# Sheet2.net
KiCad netlist of a schematic drawn in Altium Designer
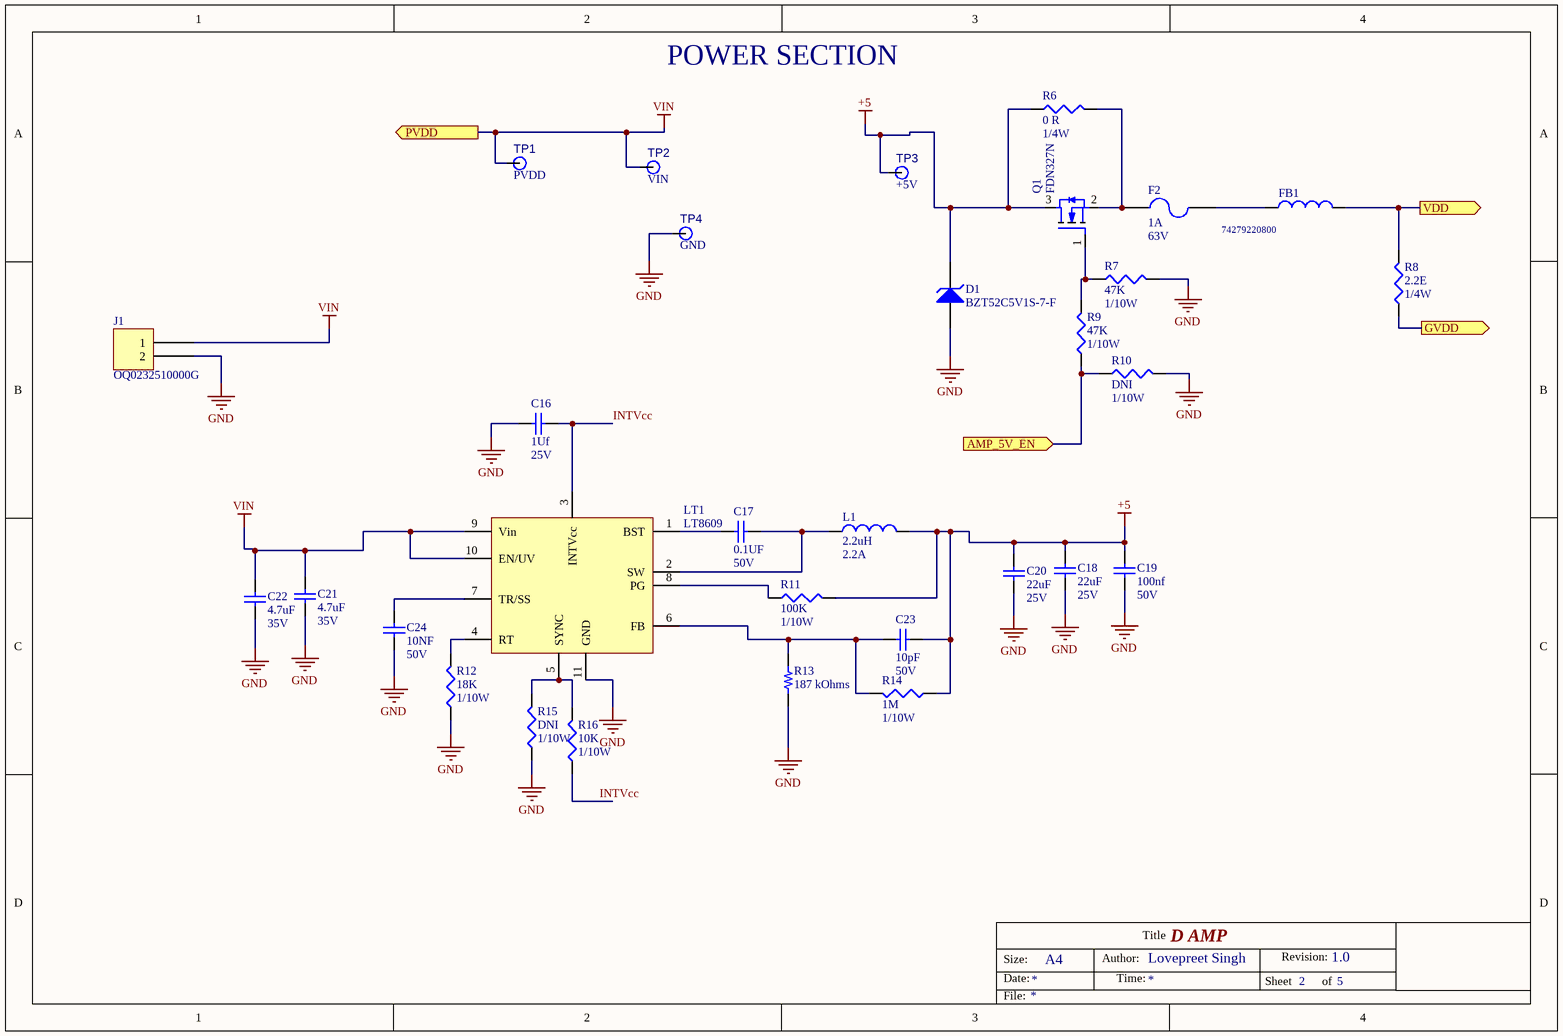
[diagram p0: Sheet2.SchDoc]

(export (version "E")
  (design (tool "Eeschema 10.0.6"))
  (components
    (comp (ref "C16")
      (value "1Uf")
      (footprint "C0603")
      (description "CAP MLCC SMD 25V 1uF 10% X7R 0603")
      (fields (field (name "VRATING") "25V"))
      (libsource (lib "Database_Libs1") (part "CAP_NPOL"))
    )
    (comp (ref "C17")
      (value "0.1UF")
      (footprint "2P0603R")
      (description "CAP CER 0.1UF 10% 50V X7R 0603")
      (fields (field (name "VRATING") "50V"))
      (libsource (lib "Database_Libs1") (part "CAP_NPOL"))
    )
    (comp (ref "C18")
      (value "22uF")
      (footprint "C1206")
      (description "CAP CER 22uF 20% 25V X5R 1206")
      (fields (field (name "VRATING") "25V"))
      (libsource (lib "Database_Libs1") (part "CAP_NPOL"))
    )
    (comp (ref "C19")
      (value "100nf")
      (footprint "C0603")
      (description "CAP CER 100NF 10% 50V X7R 0603")
      (fields (field (name "VRATING") "50V"))
      (libsource (lib "Database_Libs1") (part "CAP_NPOL"))
    )
    (comp (ref "C20")
      (value "22uF")
      (footprint "C1206")
      (description "CAP CER 22uF 20% 25V X5R 1206")
      (fields (field (name "VRATING") "25V"))
      (libsource (lib "Database_Libs1") (part "CAP_NPOL"))
    )
    (comp (ref "C21")
      (value "4.7uF")
      (footprint "C0603")
      (description "CAP CER 4.7UF 20% 35V X5R 0603")
      (fields (field (name "VRATING") "35V"))
      (libsource (lib "Database_Libs1") (part "CAP_NPOL"))
    )
    (comp (ref "C22")
      (value "4.7uF")
      (footprint "C0603")
      (description "CAP CER 4.7UF 20% 35V X5R 0603")
      (fields (field (name "VRATING") "35V"))
      (libsource (lib "Database_Libs1") (part "CAP_NPOL"))
    )
    (comp (ref "C23")
      (value "10pF")
      (footprint "C0603")
      (description "CAP 10PF 5% 50V 0603")
      (fields (field (name "VRATING") "50V"))
      (libsource (lib "Database_Libs1") (part "CAP_NPOL"))
    )
    (comp (ref "C24")
      (value "10NF")
      (footprint "C0603")
      (description "CAP CER 10NF 10% 50V X7R 0603")
      (fields (field (name "VRATING") "50V"))
      (libsource (lib "Database_Libs1") (part "CAP_NPOL"))
    )
    (comp (ref "D1")
      (value "BZT52C5V1S-7-F")
      (footprint "SOD-323")
      (description "DIODE ZENER 5.1V 200MW SOD323")
      (libsource (lib "Database_Libs1") (part "DIODE_ZENER"))
    )
    (comp (ref "F2")
      (value "1A")
      (footprint "FUSE1206")
      (description "Fuse 1A 63V Slow Blow SMD 1206")
      (fields (field (name "VRATING") "63V"))
      (libsource (lib "Database_Libs1") (part "Fuse"))
    )
    (comp (ref "FB1")
      (value "74279220800")
      (footprint "L0805")
      (description "IND FERRITE CHIP 80 OHM 4A 0805")
      (libsource (lib "Database_Libs1") (part "FERRITE CHIP"))
    )
    (comp (ref "J1")
      (value "OQ0232510000G")
      (footprint "FCI 06-381-2PIN")
      (description "TERM BLOCK HDR 2POS 90DEG 3.81MM")
      (fields (field (name "MANUFACTURER") "Amphenol Anytek"))
      (libsource (lib "Celestial Altium Library - altium_library") (part "2 Pin"))
    )
    (comp (ref "L1")
      (value "2.2uH")
      (footprint "CDMC252012")
      (description "FIXED IND 2.2UH 2A 168 MOHM SMD")
      (fields (field (name "IRATING") "2.2A"))
      (libsource (lib "Database_Libs1") (part "INDUCTOR"))
    )
    (comp (ref "LT1")
      (value "LT8609")
      (footprint "MSOP-10")
      (description "IC SWTCH REG O/P ADJ 3A I/P 4.5V-42V SMD 10MSOP")
      (libsource (lib "Database_Libs1") (part "LT8609"))
    )
    (comp (ref "Q1")
      (value "FDN327N")
      (footprint "SOT23_123")
      (description "MOSFET N-CH 20V 2A SSOT-3")
      (libsource (lib "Database_Libs1") (part "MOSFET N-CH, 20V, 1.3A SOT-23"))
    )
    (comp (ref "R6")
      (value "0 R")
      (footprint "R1206")
      (description "RES SMD 0E 5% 1/4W 1206")
      (fields (field (name "PRATING") "1/4W"))
      (libsource (lib "Database_Libs1") (part "RES"))
    )
    (comp (ref "R7")
      (value "47K")
      (footprint "R0603")
      (description "RES SMD  47K 1% 1/10W 0603")
      (fields (field (name "PRATING") "1/10W"))
      (libsource (lib "Database_Libs1") (part "RES"))
    )
    (comp (ref "R8")
      (value "2.2E")
      (footprint "R1206")
      (description "RES SMD 2.2E 1% 1/4W 1206")
      (fields (field (name "PRATING") "1/4W"))
      (libsource (lib "Database_Libs1") (part "RES"))
    )
    (comp (ref "R9")
      (value "47K")
      (footprint "R0603")
      (description "RES SMD  47K 1% 1/10W 0603")
      (fields (field (name "PRATING") "1/10W"))
      (libsource (lib "Database_Libs1") (part "RES"))
    )
    (comp (ref "R10")
      (value "DNI")
      (footprint "R0603")
      (description "RES SMD DNI 0603")
      (fields (field (name "PRATING") "1/10W"))
      (libsource (lib "Database_Libs1") (part "RES_DNI"))
    )
    (comp (ref "R11")
      (value "100K")
      (footprint "R0603")
      (description "RES SMD 100K 1% 1/10W 0603")
      (fields (field (name "PRATING") "1/10W"))
      (libsource (lib "Database_Libs1") (part "RES"))
    )
    (comp (ref "R12")
      (value "18K")
      (footprint "R0603")
      (description "RES 18K OHM 1% 1/10W 0603")
      (fields (field (name "PRATING") "1/10W"))
      (libsource (lib "Database_Libs1") (part "RES"))
    )
    (comp (ref "R13")
      (value "187 kOhms")
      (footprint "RES 0603_1608")
      (description "RES SMD 187K OHM 0.5% 1/10W 0603")
      (fields (field (name "PART NUMBER") "RT0603DRE07187KL") (field (name "MANUFACTURER") "Yageo"))
      (libsource (lib "Celestial Altium Library - altium_library") (part "Resistor"))
    )
    (comp (ref "R14")
      (value "1M")
      (footprint "R0603")
      (description "RES SMD 1M 1% 1/10W 0603")
      (fields (field (name "PRATING") "1/10W"))
      (libsource (lib "Database_Libs1") (part "RES"))
    )
    (comp (ref "R15")
      (value "DNI")
      (footprint "R0603")
      (description "RES SMD DNI 0603")
      (fields (field (name "PRATING") "1/10W"))
      (libsource (lib "Database_Libs1") (part "RES_DNI"))
    )
    (comp (ref "R16")
      (value "10K")
      (footprint "R0603")
      (description "RES SMD 10K 1% 1/10W 0603")
      (fields (field (name "PRATING") "1/10W"))
      (libsource (lib "Database_Libs1") (part "RES"))
    )
    (comp (ref "TP1")
      (value "PVDD")
      (footprint "TP_THROUGH")
      (description "TEST_POINT_THROUGH")
      (libsource (lib "Database_Libs1") (part "TEST_POINT_THROUGH"))
    )
    (comp (ref "TP2")
      (value "VIN")
      (footprint "TP_THROUGH")
      (description "TEST_POINT_THROUGH")
      (libsource (lib "Database_Libs1") (part "TEST_POINT_THROUGH"))
    )
    (comp (ref "TP3")
      (value "+5V")
      (footprint "TP_THROUGH")
      (description "TEST_POINT_THROUGH")
      (libsource (lib "Database_Libs1") (part "TEST_POINT_THROUGH"))
    )
    (comp (ref "TP4")
      (value "GND")
      (footprint "TP_THROUGH")
      (description "TEST_POINT_THROUGH")
      (libsource (lib "Database_Libs1") (part "TEST_POINT_THROUGH"))
    )
  )
  (nets
    (net (code "1") (name "+5") (class "Default")
      (node (ref "C18") (pin "2") (pinfunction "2_2") (pintype "passive"))
      (node (ref "C19") (pin "2") (pinfunction "2_2") (pintype "passive"))
      (node (ref "C20") (pin "2") (pinfunction "2_2") (pintype "passive"))
      (node (ref "C23") (pin "2") (pinfunction "2_2") (pintype "passive"))
      (node (ref "D1") (pin "K") (pinfunction "K_K") (pintype "passive"))
      (node (ref "L1") (pin "2") (pinfunction "2_2") (pintype "passive"))
      (node (ref "Q1") (pin "3") (pinfunction "D_3") (pintype "passive"))
      (node (ref "R11") (pin "2") (pinfunction "2_2") (pintype "passive"))
      (node (ref "R14") (pin "1") (pinfunction "1_1") (pintype "passive"))
      (node (ref "R6") (pin "1") (pinfunction "1_1") (pintype "passive"))
      (node (ref "TP3") (pin "1") (pinfunction "1_1") (pintype "passive"))
    )
    (net (code "2") (name "/AMP_5V_EN") (class "Default")
      (node (ref "R10") (pin "1") (pinfunction "1_1") (pintype "passive"))
      (node (ref "R9") (pin "1") (pinfunction "1_1") (pintype "passive"))
    )
    (net (code "3") (name "/GVDD") (class "Default")
      (node (ref "R8") (pin "1") (pinfunction "1_1") (pintype "passive"))
    )
    (net (code "4") (name "/INTVcc") (class "Default")
      (node (ref "C16") (pin "2") (pinfunction "2_2") (pintype "passive"))
      (node (ref "LT1") (pin "3") (pinfunction "INTVcc_3") (pintype "passive"))
      (node (ref "R16") (pin "1") (pinfunction "1_1") (pintype "passive"))
    )
    (net (code "5") (name "/VDD") (class "Default")
      (node (ref "FB1") (pin "2") (pinfunction "2_2") (pintype "passive"))
      (node (ref "R8") (pin "2") (pinfunction "2_2") (pintype "passive"))
    )
    (net (code "6") (name "GND") (class "Default")
      (node (ref "C16") (pin "1") (pinfunction "1_1") (pintype "passive"))
      (node (ref "C18") (pin "1") (pinfunction "1_1") (pintype "passive"))
      (node (ref "C19") (pin "1") (pinfunction "1_1") (pintype "passive"))
      (node (ref "C20") (pin "1") (pinfunction "1_1") (pintype "passive"))
      (node (ref "C21") (pin "1") (pinfunction "1_1") (pintype "passive"))
      (node (ref "C22") (pin "1") (pinfunction "1_1") (pintype "passive"))
      (node (ref "C24") (pin "1") (pinfunction "1_1") (pintype "passive"))
      (node (ref "D1") (pin "A") (pinfunction "A_A") (pintype "passive"))
      (node (ref "J1") (pin "2") (pinfunction "2_2") (pintype "passive"))
      (node (ref "LT1") (pin "11") (pinfunction "GND_11") (pintype "passive"))
      (node (ref "R10") (pin "2") (pinfunction "2_2") (pintype "passive"))
      (node (ref "R12") (pin "1") (pinfunction "1_1") (pintype "passive"))
      (node (ref "R13") (pin "1") (pinfunction "1_1") (pintype "passive"))
      (node (ref "R15") (pin "1") (pinfunction "1_1") (pintype "passive"))
      (node (ref "R7") (pin "2") (pinfunction "2_2") (pintype "passive"))
      (node (ref "TP4") (pin "1") (pinfunction "1_1") (pintype "passive"))
    )
    (net (code "7") (name "Net-(F2-Pad2)") (class "Default")
      (node (ref "F2") (pin "2") (pinfunction "2_2") (pintype "passive"))
      (node (ref "FB1") (pin "1") (pinfunction "1_1") (pintype "passive"))
    )
    (net (code "8") (name "Net-(LT1-BST)") (class "Default")
      (node (ref "C17") (pin "1") (pinfunction "1_1") (pintype "passive"))
      (node (ref "LT1") (pin "1") (pinfunction "BST_1") (pintype "passive"))
    )
    (net (code "9") (name "Net-(LT1-FB)") (class "Default")
      (node (ref "C23") (pin "1") (pinfunction "1_1") (pintype "passive"))
      (node (ref "LT1") (pin "6") (pinfunction "FB_6") (pintype "passive"))
      (node (ref "R13") (pin "2") (pinfunction "2_2") (pintype "passive"))
      (node (ref "R14") (pin "2") (pinfunction "2_2") (pintype "passive"))
    )
    (net (code "10") (name "Net-(LT1-PG)") (class "Default")
      (node (ref "LT1") (pin "8") (pinfunction "PG_8") (pintype "passive"))
      (node (ref "R11") (pin "1") (pinfunction "1_1") (pintype "passive"))
    )
    (net (code "11") (name "Net-(LT1-RT)") (class "Default")
      (node (ref "LT1") (pin "4") (pinfunction "RT_4") (pintype "passive"))
      (node (ref "R12") (pin "2") (pinfunction "2_2") (pintype "passive"))
    )
    (net (code "12") (name "Net-(LT1-SW)") (class "Default")
      (node (ref "C17") (pin "2") (pinfunction "2_2") (pintype "passive"))
      (node (ref "L1") (pin "1") (pinfunction "1_1") (pintype "passive"))
      (node (ref "LT1") (pin "2") (pinfunction "SW_2") (pintype "passive"))
    )
    (net (code "13") (name "Net-(LT1-SYNC)") (class "Default")
      (node (ref "LT1") (pin "5") (pinfunction "SYNC_5") (pintype "passive"))
      (node (ref "R15") (pin "2") (pinfunction "2_2") (pintype "passive"))
      (node (ref "R16") (pin "2") (pinfunction "2_2") (pintype "passive"))
    )
    (net (code "14") (name "Net-(LT1-TR{slash}SS)") (class "Default")
      (node (ref "C24") (pin "2") (pinfunction "2_2") (pintype "passive"))
      (node (ref "LT1") (pin "7") (pinfunction "TR/SS_7") (pintype "passive"))
    )
    (net (code "15") (name "Net-(Q1-G)") (class "Default")
      (node (ref "Q1") (pin "1") (pinfunction "G_1") (pintype "passive"))
      (node (ref "R7") (pin "1") (pinfunction "1_1") (pintype "passive"))
      (node (ref "R9") (pin "2") (pinfunction "2_2") (pintype "passive"))
    )
    (net (code "16") (name "Net-(Q1-S)") (class "Default")
      (node (ref "F2") (pin "1") (pinfunction "1_1") (pintype "passive"))
      (node (ref "Q1") (pin "2") (pinfunction "S_2") (pintype "passive"))
      (node (ref "R6") (pin "2") (pinfunction "2_2") (pintype "passive"))
    )
    (net (code "17") (name "VIN") (class "Default")
      (node (ref "C21") (pin "2") (pinfunction "2_2") (pintype "passive"))
      (node (ref "C22") (pin "2") (pinfunction "2_2") (pintype "passive"))
      (node (ref "J1") (pin "1") (pinfunction "1_1") (pintype "passive"))
      (node (ref "LT1") (pin "10") (pinfunction "EN/UV_10") (pintype "passive"))
      (node (ref "LT1") (pin "9") (pinfunction "Vin_9") (pintype "passive"))
      (node (ref "TP1") (pin "1") (pinfunction "1_1") (pintype "passive"))
      (node (ref "TP2") (pin "1") (pinfunction "1_1") (pintype "passive"))
    )
  )
)
